# Motor_Driver.net
KiCad netlist of a schematic drawn in EAGLE
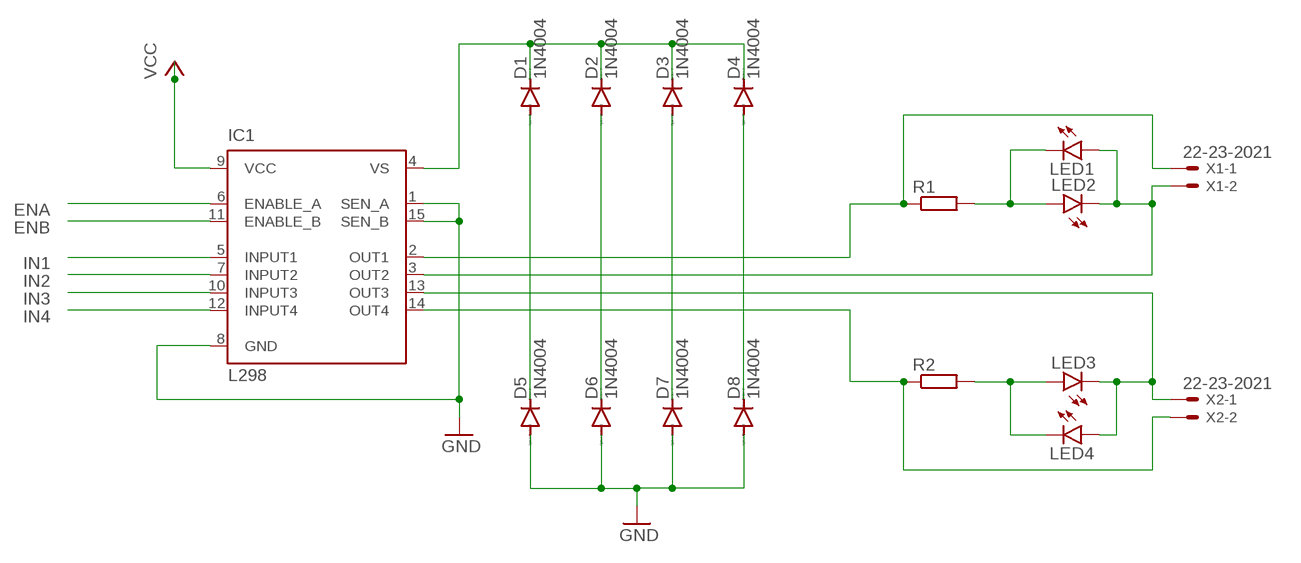
[diagram p0: schematic, sheet 1]

(export (version "E")
  (design (tool "Eeschema 10.0.6"))
  (components
    (comp (ref "D1")
      (value "1N4004")
      (footprint "eagle-import:DO41-10")
      (libsource (lib "eagle-import") (part "1N4004"))
    )
    (comp (ref "D2")
      (value "1N4004")
      (footprint "eagle-import:DO41-10")
      (libsource (lib "eagle-import") (part "1N4004"))
    )
    (comp (ref "D3")
      (value "1N4004")
      (footprint "eagle-import:DO41-10")
      (libsource (lib "eagle-import") (part "1N4004"))
    )
    (comp (ref "D4")
      (value "1N4004")
      (footprint "eagle-import:DO41-10")
      (libsource (lib "eagle-import") (part "1N4004"))
    )
    (comp (ref "D5")
      (value "1N4004")
      (footprint "eagle-import:DO41-10")
      (libsource (lib "eagle-import") (part "1N4004"))
    )
    (comp (ref "D6")
      (value "1N4004")
      (footprint "eagle-import:DO41-10")
      (libsource (lib "eagle-import") (part "1N4004"))
    )
    (comp (ref "D7")
      (value "1N4004")
      (footprint "eagle-import:DO41-10")
      (libsource (lib "eagle-import") (part "1N4004"))
    )
    (comp (ref "D8")
      (value "1N4004")
      (footprint "eagle-import:DO41-10")
      (libsource (lib "eagle-import") (part "1N4004"))
    )
    (comp (ref "IC1")
      (value "L298")
      (footprint "eagle-import:MULTIWATT-15")
      (fields (field (name "MPN") "L298N"))
      (libsource (lib "eagle-import") (part "L298"))
    )
    (comp (ref "LED1")
      (value "LEDCHIP-LED0603")
      (footprint "eagle-import:CHIP-LED0603")
      (libsource (lib "eagle-import") (part "LEDCHIP-LED0603"))
    )
    (comp (ref "LED2")
      (value "LEDCHIP-LED0603")
      (footprint "eagle-import:CHIP-LED0603")
      (libsource (lib "eagle-import") (part "LEDCHIP-LED0603"))
    )
    (comp (ref "LED3")
      (value "LEDCHIP-LED0603")
      (footprint "eagle-import:CHIP-LED0603")
      (libsource (lib "eagle-import") (part "LEDCHIP-LED0603"))
    )
    (comp (ref "LED4")
      (value "LEDCHIP-LED0603")
      (footprint "eagle-import:CHIP-LED0603")
      (libsource (lib "eagle-import") (part "LEDCHIP-LED0603"))
    )
    (comp (ref "R1")
      (value "R-EU_R0603")
      (footprint "eagle-import:R0603")
      (libsource (lib "eagle-import") (part "R-EU_R0603"))
    )
    (comp (ref "R2")
      (value "R-EU_R0603")
      (footprint "eagle-import:R0603")
      (libsource (lib "eagle-import") (part "R-EU_R0603"))
    )
    (comp (ref "X1")
      (value "22-23-2021")
      (footprint "eagle-import:22-23-2021")
      (fields (field (name "MF") "MOLEX"))
      (libsource (lib "eagle-import") (part "22-23-2021"))
    )
    (comp (ref "X2")
      (value "22-23-2021")
      (footprint "eagle-import:22-23-2021")
      (fields (field (name "MF") "MOLEX"))
      (libsource (lib "eagle-import") (part "22-23-2021"))
    )
  )
  (nets
    (net (code "1") (name "/ENA") (class "Default")
      (node (ref "IC1") (pin "6") (pinfunction "ENABLE_A_6") (pintype "input"))
    )
    (net (code "2") (name "/ENB") (class "Default")
      (node (ref "IC1") (pin "11") (pinfunction "ENABLE_B_11") (pintype "input"))
    )
    (net (code "3") (name "/IN1") (class "Default")
      (node (ref "IC1") (pin "5") (pinfunction "INPUT1_5") (pintype "input"))
    )
    (net (code "4") (name "/IN2") (class "Default")
      (node (ref "IC1") (pin "7") (pinfunction "INPUT2_7") (pintype "input"))
    )
    (net (code "5") (name "/IN3") (class "Default")
      (node (ref "IC1") (pin "10") (pinfunction "INPUT3_10") (pintype "input"))
    )
    (net (code "6") (name "/IN4") (class "Default")
      (node (ref "IC1") (pin "12") (pinfunction "INPUT4_12") (pintype "input"))
    )
    (net (code "7") (name "GND") (class "Default")
      (node (ref "D5") (pin "A") (pinfunction "A_A") (pintype "passive"))
      (node (ref "D6") (pin "A") (pinfunction "A_A") (pintype "passive"))
      (node (ref "D7") (pin "A") (pinfunction "A_A") (pintype "passive"))
      (node (ref "D8") (pin "A") (pinfunction "A_A") (pintype "passive"))
      (node (ref "IC1") (pin "1") (pinfunction "SEN_A_1") (pintype "input"))
      (node (ref "IC1") (pin "15") (pinfunction "SEN_B_15") (pintype "input"))
      (node (ref "IC1") (pin "8") (pinfunction "GND_8") (pintype "power_in"))
    )
    (net (code "8") (name "Net-(D1-PadA)") (class "Default")
      (node (ref "D1") (pin "A") (pinfunction "A_A") (pintype "passive"))
      (node (ref "D5") (pin "C") (pinfunction "C_C") (pintype "passive"))
    )
    (net (code "9") (name "Net-(D2-PadA)") (class "Default")
      (node (ref "D2") (pin "A") (pinfunction "A_A") (pintype "passive"))
      (node (ref "D6") (pin "C") (pinfunction "C_C") (pintype "passive"))
    )
    (net (code "10") (name "Net-(D3-PadA)") (class "Default")
      (node (ref "D3") (pin "A") (pinfunction "A_A") (pintype "passive"))
      (node (ref "D7") (pin "C") (pinfunction "C_C") (pintype "passive"))
    )
    (net (code "11") (name "Net-(D4-PadA)") (class "Default")
      (node (ref "D4") (pin "A") (pinfunction "A_A") (pintype "passive"))
      (node (ref "D8") (pin "C") (pinfunction "C_C") (pintype "passive"))
    )
    (net (code "12") (name "Net-(IC1-OUT1)") (class "Default")
      (node (ref "IC1") (pin "2") (pinfunction "OUT1_2") (pintype "output"))
      (node (ref "R1") (pin "1") (pinfunction "1_1") (pintype "passive"))
      (node (ref "X1") (pin "1") (pinfunction "S_1") (pintype "passive"))
    )
    (net (code "13") (name "Net-(IC1-OUT2)") (class "Default")
      (node (ref "IC1") (pin "3") (pinfunction "OUT2_3") (pintype "output"))
      (node (ref "LED1") (pin "A") (pinfunction "A_A") (pintype "passive"))
      (node (ref "LED2") (pin "C") (pinfunction "C_C") (pintype "passive"))
      (node (ref "X1") (pin "2") (pinfunction "S_2") (pintype "passive"))
    )
    (net (code "14") (name "Net-(IC1-OUT3)") (class "Default")
      (node (ref "IC1") (pin "13") (pinfunction "OUT3_13") (pintype "output"))
      (node (ref "LED3") (pin "C") (pinfunction "C_C") (pintype "passive"))
      (node (ref "LED4") (pin "A") (pinfunction "A_A") (pintype "passive"))
      (node (ref "X2") (pin "1") (pinfunction "S_1") (pintype "passive"))
    )
    (net (code "15") (name "Net-(IC1-OUT4)") (class "Default")
      (node (ref "IC1") (pin "14") (pinfunction "OUT4_14") (pintype "output"))
      (node (ref "R2") (pin "1") (pinfunction "1_1") (pintype "passive"))
      (node (ref "X2") (pin "2") (pinfunction "S_2") (pintype "passive"))
    )
    (net (code "16") (name "Net-(IC1-VS)") (class "Default")
      (node (ref "D1") (pin "C") (pinfunction "C_C") (pintype "passive"))
      (node (ref "D2") (pin "C") (pinfunction "C_C") (pintype "passive"))
      (node (ref "D3") (pin "C") (pinfunction "C_C") (pintype "passive"))
      (node (ref "D4") (pin "C") (pinfunction "C_C") (pintype "passive"))
      (node (ref "IC1") (pin "4") (pinfunction "VS_4") (pintype "power_in"))
    )
    (net (code "17") (name "Net-(LED1-PadC)") (class "Default")
      (node (ref "LED1") (pin "C") (pinfunction "C_C") (pintype "passive"))
      (node (ref "LED2") (pin "A") (pinfunction "A_A") (pintype "passive"))
      (node (ref "R1") (pin "2") (pinfunction "2_2") (pintype "passive"))
    )
    (net (code "18") (name "Net-(LED3-PadA)") (class "Default")
      (node (ref "LED3") (pin "A") (pinfunction "A_A") (pintype "passive"))
      (node (ref "LED4") (pin "C") (pinfunction "C_C") (pintype "passive"))
      (node (ref "R2") (pin "2") (pinfunction "2_2") (pintype "passive"))
    )
    (net (code "19") (name "VCC") (class "Default")
      (node (ref "IC1") (pin "9") (pinfunction "VCC_9") (pintype "power_in"))
    )
  )
)
